# Microphone-Other_Parts.net
KiCad netlist of a schematic drawn in Altium Designer
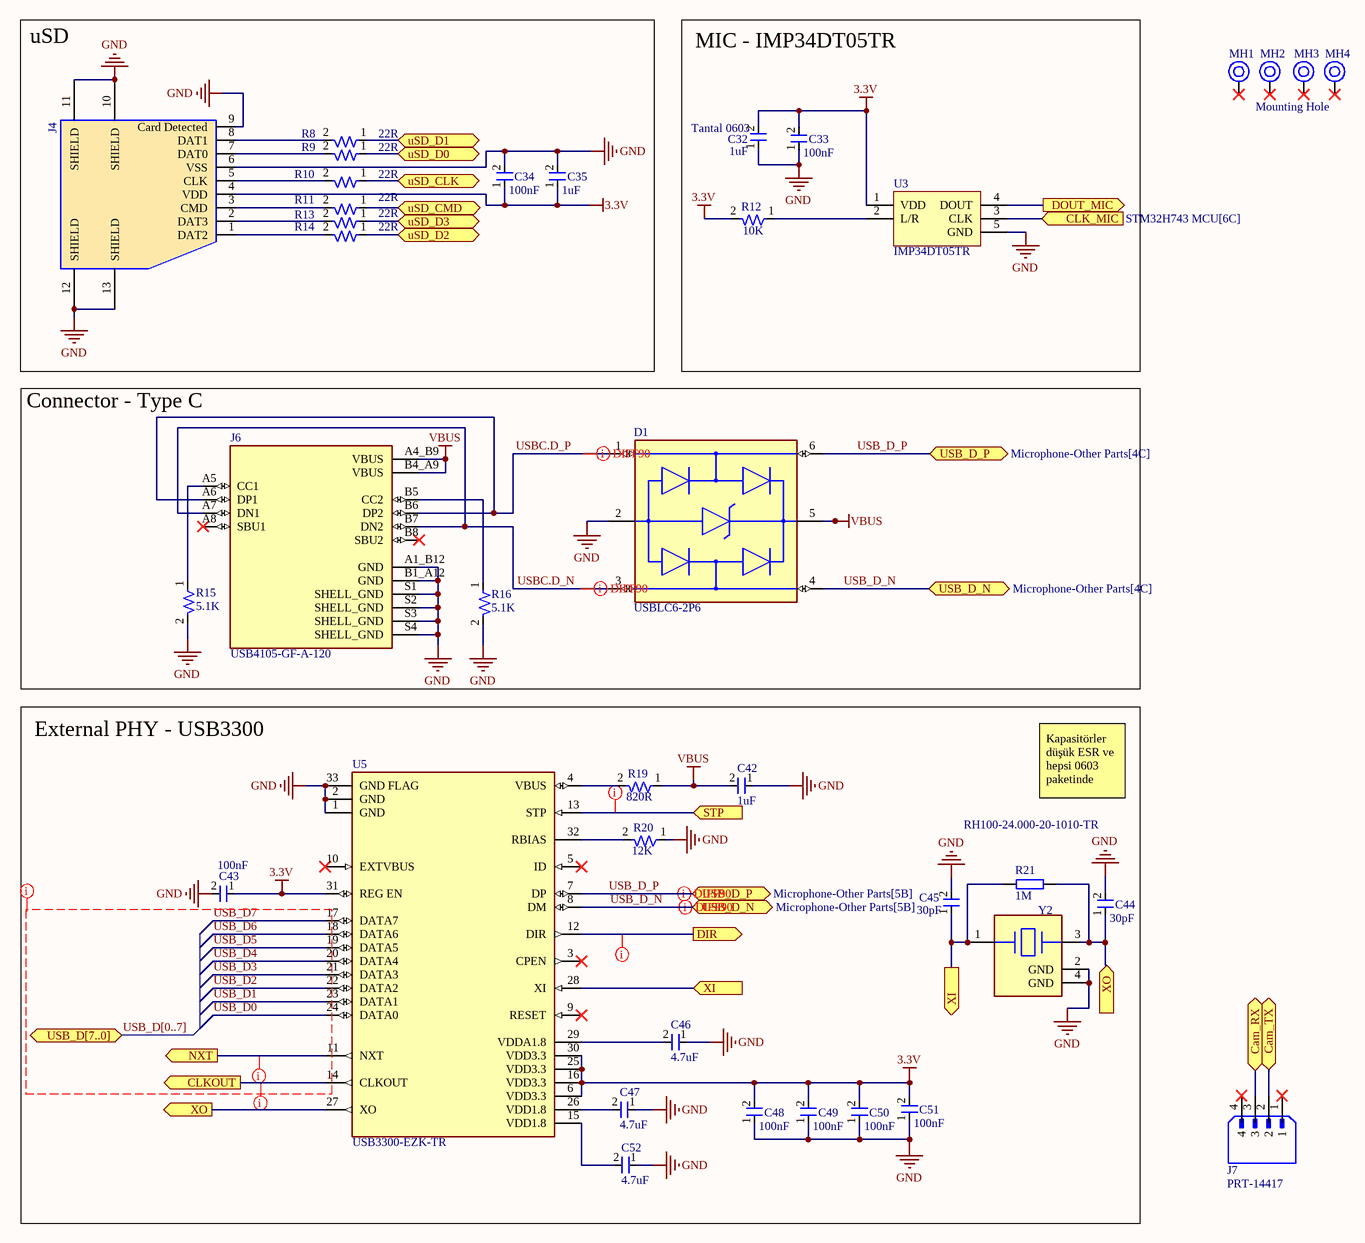
[diagram p0: Microphone-Other Parts.SchDoc]

(export (version "E")
  (design (tool "Eeschema 10.0.6"))
  (components
    (comp (ref "C32")
      (value "Tantal 0603")
      (footprint "0603 Cap")
      (fields (field (name "C") "1uF"))
      (libsource (lib "VoltaRoket") (part "0603 Cap"))
    )
    (comp (ref "C33")
      (value "0603")
      (footprint "0603 Cap")
      (fields (field (name "C") "100nF"))
      (libsource (lib "VoltaRoket") (part "0603 Cap"))
    )
    (comp (ref "C34")
      (value "0603")
      (footprint "0603 Cap")
      (fields (field (name "C") "100nF"))
      (libsource (lib "VoltaRoket") (part "0603 Cap"))
    )
    (comp (ref "C35")
      (value "0603")
      (footprint "0603 Cap")
      (fields (field (name "C") "1uF"))
      (libsource (lib "VoltaRoket") (part "0603 Cap"))
    )
    (comp (ref "C42")
      (value "0603")
      (footprint "0603 Cap")
      (fields (field (name "C") "1uF"))
      (libsource (lib "VoltaRoket") (part "0603 Cap"))
    )
    (comp (ref "C43")
      (value "0603")
      (footprint "0603 Cap")
      (fields (field (name "C") "100nF"))
      (libsource (lib "VoltaRoket") (part "0603 Cap"))
    )
    (comp (ref "C44")
      (value "0603")
      (footprint "0603 Cap")
      (fields (field (name "C") "30pF"))
      (libsource (lib "VoltaRoket") (part "0603 Cap"))
    )
    (comp (ref "C45")
      (value "0603")
      (footprint "0603 Cap")
      (fields (field (name "C") "30pF"))
      (libsource (lib "VoltaRoket") (part "0603 Cap"))
    )
    (comp (ref "C46")
      (value "0603")
      (footprint "0603 Cap")
      (fields (field (name "C") "4.7uF"))
      (libsource (lib "VoltaRoket") (part "0603 Cap"))
    )
    (comp (ref "C47")
      (value "0603")
      (footprint "0603 Cap")
      (fields (field (name "C") "4.7uF"))
      (libsource (lib "VoltaRoket") (part "0603 Cap"))
    )
    (comp (ref "C48")
      (value "0603")
      (footprint "0603 Cap")
      (fields (field (name "C") "100nF"))
      (libsource (lib "VoltaRoket") (part "0603 Cap"))
    )
    (comp (ref "C49")
      (value "0603")
      (footprint "0603 Cap")
      (fields (field (name "C") "100nF"))
      (libsource (lib "VoltaRoket") (part "0603 Cap"))
    )
    (comp (ref "C50")
      (value "0603")
      (footprint "0603 Cap")
      (fields (field (name "C") "100nF"))
      (libsource (lib "VoltaRoket") (part "0603 Cap"))
    )
    (comp (ref "C51")
      (value "0603")
      (footprint "0603 Cap")
      (fields (field (name "C") "100nF"))
      (libsource (lib "VoltaRoket") (part "0603 Cap"))
    )
    (comp (ref "C52")
      (value "0603")
      (footprint "0603 Cap")
      (fields (field (name "C") "4.7uF"))
      (libsource (lib "VoltaRoket") (part "0603 Cap"))
    )
    (comp (ref "D1")
      (value "USBLC6-2P6")
      (footprint "FP-SOT-666-MFG")
      (description "TVS DIODE 5.25V 17V SOT666")
      (libsource (lib "Altium Content Vault") (part "c871e55f7e3243d341edbd671b98d92"))
    )
    (comp (ref "J4")
      (value "KLS1-TF-003-R")
      (footprint "KLS1-TF-003-R")
      (description "KLS1-TF-003-R                     SD CARD CONNECTOR")
      (libsource (lib "VoltaRoket") (part "KLS1-TF-003-R"))
    )
    (comp (ref "J6")
      (value "USB4105-GF-A-120")
      (footprint "GCT_USB4105-GF-A-120")
      (fields (field (name "MF") "Global Connector Technology") (field (name "MP") "USB4105GFA120"))
      (libsource (lib "USB4105-GF-A-120") (part "USB4105-GF-A-120"))
    )
    (comp (ref "J7")
      (value "PRT-14417")
      (footprint "SPARKFUN_PRT-14417")
      (description "QWIIC JST CONNECTOR - SMD 4-PIN")
      (fields (field (name "MF") "SparkFun Electronics"))
      (libsource (lib "PRT-14417 (1)") (part "PRT-14417"))
    )
    (comp (ref "MH1")
      (value "Mounting Hole")
      (footprint "MOUNTING")
      (fields (field (name "MANUFACTURER PART NUMBER") "NA"))
      (libsource (lib "ESTEEMPCBLIB") (part "MH_3.5H_6D"))
    )
    (comp (ref "MH2")
      (value "Mounting Hole")
      (footprint "MOUNTING")
      (fields (field (name "MANUFACTURER PART NUMBER") "NA"))
      (libsource (lib "ESTEEMPCBLIB") (part "MH_3.5H_6D"))
    )
    (comp (ref "MH3")
      (value "Mounting Hole")
      (footprint "MOUNTING")
      (fields (field (name "MANUFACTURER PART NUMBER") "NA"))
      (libsource (lib "ESTEEMPCBLIB") (part "MH_3.5H_6D"))
    )
    (comp (ref "MH4")
      (value "Mounting Hole")
      (footprint "MOUNTING")
      (fields (field (name "MANUFACTURER PART NUMBER") "NA"))
      (libsource (lib "ESTEEMPCBLIB") (part "MH_3.5H_6D"))
    )
    (comp (ref "R8")
      (value "0603")
      (footprint "0603 Res")
      (fields (field (name "R") "22R"))
      (libsource (lib "VoltaRoket") (part "0603 Res"))
    )
    (comp (ref "R9")
      (value "0603")
      (footprint "0603 Res")
      (fields (field (name "R") "22R"))
      (libsource (lib "VoltaRoket") (part "0603 Res"))
    )
    (comp (ref "R10")
      (value "0603")
      (footprint "0603 Res")
      (fields (field (name "R") "22R"))
      (libsource (lib "VoltaRoket") (part "0603 Res"))
    )
    (comp (ref "R11")
      (value "0603")
      (footprint "0603 Res")
      (fields (field (name "R") "22R"))
      (libsource (lib "VoltaRoket") (part "0603 Res"))
    )
    (comp (ref "R12")
      (value "0603")
      (footprint "0603 Res")
      (fields (field (name "R") "10K"))
      (libsource (lib "VoltaRoket") (part "0603 Res"))
    )
    (comp (ref "R13")
      (value "0603")
      (footprint "0603 Res")
      (fields (field (name "R") "22R"))
      (libsource (lib "VoltaRoket") (part "0603 Res"))
    )
    (comp (ref "R14")
      (value "0603")
      (footprint "0603 Res")
      (fields (field (name "R") "22R"))
      (libsource (lib "VoltaRoket") (part "0603 Res"))
    )
    (comp (ref "R15")
      (value "0603")
      (footprint "0603 Res")
      (fields (field (name "R") "5.1K"))
      (libsource (lib "VoltaRoket") (part "0603 Res"))
    )
    (comp (ref "R16")
      (value "0603")
      (footprint "0603 Res")
      (fields (field (name "R") "5.1K"))
      (libsource (lib "VoltaRoket") (part "0603 Res"))
    )
    (comp (ref "R19")
      (value "0603")
      (footprint "0603 Res")
      (fields (field (name "R") "820R"))
      (libsource (lib "VoltaRoket") (part "0603 Res"))
    )
    (comp (ref "R20")
      (value "0603")
      (footprint "0603 Res")
      (fields (field (name "R") "12K"))
      (libsource (lib "VoltaRoket") (part "0603 Res"))
    )
    (comp (ref "R21")
      (value "1M")
      (footprint "RES_0603")
      (description "Resistor SMD 0603")
      (libsource (lib "Phills_Lib") (part "RES_0603"))
    )
    (comp (ref "U3")
      (value "IMP34DT05TR")
      (footprint "HCLGA-4_53_137_15X37_SMD")
      (description "MEMS Microphones AUTO & INDUSTRIAL SENSORS")
      (fields (field (name "MANUFACTURER") "STMicroelectronics"))
      (libsource (lib "ESTEEMPCBLIB") (part "IC_IMP34DT05TR"))
    )
    (comp (ref "U5")
      (value "USB3300-EZK-TR")
      (footprint "FP-32QFN-3304-5X5B-MFG")
      (description "IC CONTROLLER USB 32QFN")
      (fields
        (field (name "MANUFACTURER") "Microchip")
        (field (name "OCTOPART") "https://octopart.com/usb3300-ezk-tr-microchip-24995444")
      )
      (libsource (lib "Altium Content Vault") (part "4aa10816561f241a170599044d3291b"))
    )
    (comp (ref "Y2")
      (value "RH100-24.000-20-1010-TR")
      (footprint "FP-ABM8AIG-MFG")
      (description "Crystal 24MHz ±20ppm (Tol) ±50ppm (Stability) 12pF FUND 50Ω Automotive 4-Pin Ultra Mini-CSMD T/R")
      (libsource (lib "Altium Content Vault") (part "5645ab55de99a04feaa93ac4102b7fe"))
    )
  )
  (nets
    (net (code "1") (name "/CLKOUT") (class "Default")
      (node (ref "U5") (pin "14") (pinfunction "CLKOUT_14") (pintype "output"))
    )
    (net (code "2") (name "/CLK_MIC") (class "Default")
      (node (ref "U3") (pin "3") (pinfunction "CLK_3") (pintype "passive"))
    )
    (net (code "3") (name "/Cam_RX") (class "Default")
      (node (ref "J7") (pin "3") (pinfunction "3_3") (pintype "passive"))
    )
    (net (code "4") (name "/Cam_TX") (class "Default")
      (node (ref "J7") (pin "2") (pinfunction "2_2") (pintype "passive"))
    )
    (net (code "5") (name "/DIR") (class "Default")
      (node (ref "U5") (pin "12") (pinfunction "DIR_12") (pintype "output"))
    )
    (net (code "6") (name "/DOUT_MIC") (class "Default")
      (node (ref "U3") (pin "4") (pinfunction "DOUT_4") (pintype "passive"))
    )
    (net (code "7") (name "/NXT") (class "Default")
      (node (ref "U5") (pin "11") (pinfunction "NXT_11") (pintype "output"))
    )
    (net (code "8") (name "/STP") (class "Default")
      (node (ref "U5") (pin "13") (pinfunction "STP_13") (pintype "input"))
    )
    (net (code "9") (name "/USBC.D_N") (class "Default")
      (node (ref "D1") (pin "3") (pinfunction "I/O2_3") (pintype "bidirectional"))
      (node (ref "J6") (pin "A7") (pinfunction "DN1_A7") (pintype "bidirectional"))
      (node (ref "J6") (pin "B7") (pinfunction "DN2_B7") (pintype "bidirectional"))
    )
    (net (code "10") (name "/USBC.D_P") (class "Default")
      (node (ref "D1") (pin "1") (pinfunction "I/O1_1") (pintype "bidirectional"))
      (node (ref "J6") (pin "A6") (pinfunction "DP1_A6") (pintype "bidirectional"))
      (node (ref "J6") (pin "B6") (pinfunction "DP2_B6") (pintype "bidirectional"))
    )
    (net (code "11") (name "/USB_D0") (class "Default")
      (node (ref "U5") (pin "24") (pinfunction "DATA0_24") (pintype "bidirectional"))
    )
    (net (code "12") (name "/USB_D1") (class "Default")
      (node (ref "U5") (pin "23") (pinfunction "DATA1_23") (pintype "bidirectional"))
    )
    (net (code "13") (name "/USB_D2") (class "Default")
      (node (ref "U5") (pin "22") (pinfunction "DATA2_22") (pintype "bidirectional"))
    )
    (net (code "14") (name "/USB_D3") (class "Default")
      (node (ref "U5") (pin "21") (pinfunction "DATA3_21") (pintype "bidirectional"))
    )
    (net (code "15") (name "/USB_D4") (class "Default")
      (node (ref "U5") (pin "20") (pinfunction "DATA4_20") (pintype "bidirectional"))
    )
    (net (code "16") (name "/USB_D5") (class "Default")
      (node (ref "U5") (pin "19") (pinfunction "DATA5_19") (pintype "bidirectional"))
    )
    (net (code "17") (name "/USB_D6") (class "Default")
      (node (ref "U5") (pin "18") (pinfunction "DATA6_18") (pintype "bidirectional"))
    )
    (net (code "18") (name "/USB_D7") (class "Default")
      (node (ref "U5") (pin "17") (pinfunction "DATA7_17") (pintype "bidirectional"))
    )
    (net (code "20") (name "/USB_D_N") (class "Default")
      (node (ref "D1") (pin "4") (pinfunction "I/O2_4") (pintype "bidirectional"))
      (node (ref "U5") (pin "8") (pinfunction "DM_8") (pintype "bidirectional"))
    )
    (net (code "21") (name "/USB_D_P") (class "Default")
      (node (ref "D1") (pin "6") (pinfunction "I/O1_6") (pintype "bidirectional"))
      (node (ref "U5") (pin "7") (pinfunction "DP_7") (pintype "bidirectional"))
    )
    (net (code "22") (name "/XI") (class "Default")
      (node (ref "C45") (pin "1") (pinfunction "1_1") (pintype "passive"))
      (node (ref "R21") (pin "1") (pinfunction "1_1") (pintype "passive"))
      (node (ref "U5") (pin "28") (pinfunction "XI_28") (pintype "input"))
      (node (ref "Y2") (pin "1") (pinfunction "1_1") (pintype "passive"))
    )
    (net (code "23") (name "/XO") (class "Default")
      (node (ref "C44") (pin "1") (pinfunction "1_1") (pintype "passive"))
      (node (ref "R21") (pin "2") (pinfunction "2_2") (pintype "passive"))
      (node (ref "U5") (pin "27") (pinfunction "XO_27") (pintype "output"))
      (node (ref "Y2") (pin "3") (pinfunction "3_3") (pintype "passive"))
    )
    (net (code "24") (name "/uSD_CLK") (class "Default")
      (node (ref "R10") (pin "1") (pinfunction "1_1") (pintype "passive"))
    )
    (net (code "25") (name "/uSD_CMD") (class "Default")
      (node (ref "R11") (pin "1") (pinfunction "1_1") (pintype "passive"))
    )
    (net (code "26") (name "/uSD_D0") (class "Default")
      (node (ref "R9") (pin "1") (pinfunction "1_1") (pintype "passive"))
    )
    (net (code "27") (name "/uSD_D1") (class "Default")
      (node (ref "R8") (pin "1") (pinfunction "1_1") (pintype "passive"))
    )
    (net (code "28") (name "/uSD_D2") (class "Default")
      (node (ref "R14") (pin "1") (pinfunction "1_1") (pintype "passive"))
    )
    (net (code "29") (name "/uSD_D3") (class "Default")
      (node (ref "R13") (pin "1") (pinfunction "1_1") (pintype "passive"))
    )
    (net (code "30") (name "3.3V") (class "Default")
      (node (ref "C32") (pin "2") (pinfunction "2_2") (pintype "passive"))
      (node (ref "C33") (pin "2") (pinfunction "2_2") (pintype "passive"))
      (node (ref "C34") (pin "1") (pinfunction "1_1") (pintype "passive"))
      (node (ref "C35") (pin "1") (pinfunction "1_1") (pintype "passive"))
      (node (ref "C43") (pin "1") (pinfunction "1_1") (pintype "passive"))
      (node (ref "C48") (pin "2") (pinfunction "2_2") (pintype "passive"))
      (node (ref "C49") (pin "2") (pinfunction "2_2") (pintype "passive"))
      (node (ref "C50") (pin "2") (pinfunction "2_2") (pintype "passive"))
      (node (ref "C51") (pin "2") (pinfunction "2_2") (pintype "passive"))
      (node (ref "J4") (pin "4") (pinfunction "VDD_4") (pintype "passive"))
      (node (ref "R12") (pin "2") (pinfunction "2_2") (pintype "passive"))
      (node (ref "U3") (pin "1") (pinfunction "VDD_1") (pintype "passive"))
      (node (ref "U5") (pin "16") (pinfunction "VDD3.3_16") (pintype "power_in"))
      (node (ref "U5") (pin "25") (pinfunction "VDD3.3_25") (pintype "power_in"))
      (node (ref "U5") (pin "30") (pinfunction "VDD3.3_30") (pintype "power_in"))
      (node (ref "U5") (pin "31") (pinfunction "REG_EN_31") (pintype "bidirectional"))
      (node (ref "U5") (pin "6") (pinfunction "VDD3.3_6") (pintype "power_in"))
    )
    (net (code "31") (name "GND") (class "Default")
      (node (ref "C32") (pin "1") (pinfunction "1_1") (pintype "passive"))
      (node (ref "C33") (pin "1") (pinfunction "1_1") (pintype "passive"))
      (node (ref "C34") (pin "2") (pinfunction "2_2") (pintype "passive"))
      (node (ref "C35") (pin "2") (pinfunction "2_2") (pintype "passive"))
      (node (ref "C42") (pin "1") (pinfunction "1_1") (pintype "passive"))
      (node (ref "C43") (pin "2") (pinfunction "2_2") (pintype "passive"))
      (node (ref "C44") (pin "2") (pinfunction "2_2") (pintype "passive"))
      (node (ref "C45") (pin "2") (pinfunction "2_2") (pintype "passive"))
      (node (ref "C46") (pin "1") (pinfunction "1_1") (pintype "passive"))
      (node (ref "C47") (pin "1") (pinfunction "1_1") (pintype "passive"))
      (node (ref "C48") (pin "1") (pinfunction "1_1") (pintype "passive"))
      (node (ref "C49") (pin "1") (pinfunction "1_1") (pintype "passive"))
      (node (ref "C50") (pin "1") (pinfunction "1_1") (pintype "passive"))
      (node (ref "C51") (pin "1") (pinfunction "1_1") (pintype "passive"))
      (node (ref "C52") (pin "1") (pinfunction "1_1") (pintype "passive"))
      (node (ref "D1") (pin "2") (pinfunction "GND_2") (pintype "power_in"))
      (node (ref "J4") (pin "10") (pinfunction "SHIELD_10") (pintype "passive"))
      (node (ref "J4") (pin "11") (pinfunction "SHIELD_11") (pintype "passive"))
      (node (ref "J4") (pin "12") (pinfunction "SHIELD_12") (pintype "passive"))
      (node (ref "J4") (pin "13") (pinfunction "SHIELD_13") (pintype "passive"))
      (node (ref "J4") (pin "6") (pinfunction "VSS_6") (pintype "passive"))
      (node (ref "J4") (pin "9") (pinfunction "Card_Detected_9") (pintype "passive"))
      (node (ref "J6") (pin "A1_B12") (pinfunction "GND_A1_B12") (pintype "power_in"))
      (node (ref "J6") (pin "B1_A12") (pinfunction "GND_B1_A12") (pintype "power_in"))
      (node (ref "J6") (pin "S1") (pinfunction "SHELL_GND_S1") (pintype "power_in"))
      (node (ref "J6") (pin "S2") (pinfunction "SHELL_GND_S2") (pintype "power_in"))
      (node (ref "J6") (pin "S3") (pinfunction "SHELL_GND_S3") (pintype "power_in"))
      (node (ref "J6") (pin "S4") (pinfunction "SHELL_GND_S4") (pintype "power_in"))
      (node (ref "R15") (pin "2") (pinfunction "2_2") (pintype "passive"))
      (node (ref "R16") (pin "2") (pinfunction "2_2") (pintype "passive"))
      (node (ref "R20") (pin "1") (pinfunction "1_1") (pintype "passive"))
      (node (ref "U3") (pin "5") (pinfunction "GND_5") (pintype "passive"))
      (node (ref "U5") (pin "1") (pinfunction "GND_1") (pintype "power_in"))
      (node (ref "U5") (pin "2") (pinfunction "GND_2") (pintype "power_in"))
      (node (ref "U5") (pin "33") (pinfunction "GND_FLAG_33") (pintype "power_in"))
      (node (ref "Y2") (pin "2") (pinfunction "GND_2") (pintype "power_in"))
      (node (ref "Y2") (pin "4") (pinfunction "GND_4") (pintype "power_in"))
    )
    (net (code "32") (name "Net-(C47-Pad2)") (class "Default")
      (node (ref "C47") (pin "2") (pinfunction "2_2") (pintype "passive"))
      (node (ref "U5") (pin "26") (pinfunction "VDD1.8_26") (pintype "power_in"))
    )
    (net (code "33") (name "Net-(C52-Pad2)") (class "Default")
      (node (ref "C52") (pin "2") (pinfunction "2_2") (pintype "passive"))
      (node (ref "U5") (pin "15") (pinfunction "VDD1.8_15") (pintype "power_in"))
    )
    (net (code "34") (name "Net-(J4-CLK)") (class "Default")
      (node (ref "J4") (pin "5") (pinfunction "CLK_5") (pintype "passive"))
      (node (ref "R10") (pin "2") (pinfunction "2_2") (pintype "passive"))
    )
    (net (code "35") (name "Net-(J4-CMD)") (class "Default")
      (node (ref "J4") (pin "3") (pinfunction "CMD_3") (pintype "passive"))
      (node (ref "R11") (pin "2") (pinfunction "2_2") (pintype "passive"))
    )
    (net (code "36") (name "Net-(J4-DAT0)") (class "Default")
      (node (ref "J4") (pin "7") (pinfunction "DAT0_7") (pintype "passive"))
      (node (ref "R9") (pin "2") (pinfunction "2_2") (pintype "passive"))
    )
    (net (code "37") (name "Net-(J4-DAT1)") (class "Default")
      (node (ref "J4") (pin "8") (pinfunction "DAT1_8") (pintype "passive"))
      (node (ref "R8") (pin "2") (pinfunction "2_2") (pintype "passive"))
    )
    (net (code "38") (name "Net-(J4-DAT2)") (class "Default")
      (node (ref "J4") (pin "1") (pinfunction "DAT2_1") (pintype "passive"))
      (node (ref "R14") (pin "2") (pinfunction "2_2") (pintype "passive"))
    )
    (net (code "39") (name "Net-(J4-DAT3)") (class "Default")
      (node (ref "J4") (pin "2") (pinfunction "DAT3_2") (pintype "passive"))
      (node (ref "R13") (pin "2") (pinfunction "2_2") (pintype "passive"))
    )
    (net (code "40") (name "Net-(J6-CC1)") (class "Default")
      (node (ref "J6") (pin "A5") (pinfunction "CC1_A5") (pintype "bidirectional"))
      (node (ref "R15") (pin "1") (pinfunction "1_1") (pintype "passive"))
    )
    (net (code "41") (name "Net-(J6-CC2)") (class "Default")
      (node (ref "J6") (pin "B5") (pinfunction "CC2_B5") (pintype "bidirectional"))
      (node (ref "R16") (pin "1") (pinfunction "1_1") (pintype "passive"))
    )
    (net (code "42") (name "Net-(U3-L{slash}R)") (class "Default")
      (node (ref "R12") (pin "1") (pinfunction "1_1") (pintype "passive"))
      (node (ref "U3") (pin "2") (pinfunction "L/R_2") (pintype "passive"))
    )
    (net (code "43") (name "Net-(U5-RBIAS)") (class "Default")
      (node (ref "R20") (pin "2") (pinfunction "2_2") (pintype "passive"))
      (node (ref "U5") (pin "32") (pinfunction "RBIAS_32") (pintype "power_in"))
    )
    (net (code "44") (name "Net-(U5-VBUS)") (class "Default")
      (node (ref "R19") (pin "2") (pinfunction "2_2") (pintype "passive"))
      (node (ref "U5") (pin "4") (pinfunction "VBUS_4") (pintype "bidirectional"))
    )
    (net (code "45") (name "Net-(U5-VDDA1.8)") (class "Default")
      (node (ref "C46") (pin "2") (pinfunction "2_2") (pintype "passive"))
      (node (ref "U5") (pin "29") (pinfunction "VDDA1.8_29") (pintype "power_in"))
    )
    (net (code "46") (name "VBUS") (class "Default")
      (node (ref "C42") (pin "2") (pinfunction "2_2") (pintype "passive"))
      (node (ref "D1") (pin "5") (pinfunction "VBUS_5") (pintype "power_in"))
      (node (ref "J6") (pin "A4_B9") (pinfunction "VBUS_A4_B9") (pintype "power_in"))
      (node (ref "J6") (pin "B4_A9") (pinfunction "VBUS_B4_A9") (pintype "power_in"))
      (node (ref "R19") (pin "1") (pinfunction "1_1") (pintype "passive"))
    )
    (net (code "47") (name "unconnected-(J6-SBU1-PadA8)") (class "Default")
      (node (ref "J6") (pin "A8") (pinfunction "SBU1_A8") (pintype "bidirectional+no_connect"))
    )
    (net (code "48") (name "unconnected-(J6-SBU2-PadB8)") (class "Default")
      (node (ref "J6") (pin "B8") (pinfunction "SBU2_B8") (pintype "bidirectional+no_connect"))
    )
    (net (code "49") (name "unconnected-(J7-Pad1)") (class "Default")
      (node (ref "J7") (pin "1") (pinfunction "1_1") (pintype "passive+no_connect"))
    )
    (net (code "50") (name "unconnected-(J7-Pad4)") (class "Default")
      (node (ref "J7") (pin "4") (pinfunction "4_4") (pintype "passive+no_connect"))
    )
    (net (code "51") (name "unconnected-(MH1-Pad1)") (class "Default")
      (node (ref "MH1") (pin "1") (pinfunction "1_1") (pintype "passive+no_connect"))
    )
    (net (code "52") (name "unconnected-(MH2-Pad1)") (class "Default")
      (node (ref "MH2") (pin "1") (pinfunction "1_1") (pintype "passive+no_connect"))
    )
    (net (code "53") (name "unconnected-(MH3-Pad1)") (class "Default")
      (node (ref "MH3") (pin "1") (pinfunction "1_1") (pintype "passive+no_connect"))
    )
    (net (code "54") (name "unconnected-(MH4-Pad1)") (class "Default")
      (node (ref "MH4") (pin "1") (pinfunction "1_1") (pintype "passive+no_connect"))
    )
    (net (code "55") (name "unconnected-(U5-CPEN-Pad3)") (class "Default")
      (node (ref "U5") (pin "3") (pinfunction "CPEN_3") (pintype "output+no_connect"))
    )
    (net (code "56") (name "unconnected-(U5-EXTVBUS-Pad10)") (class "Default")
      (node (ref "U5") (pin "10") (pinfunction "EXTVBUS_10") (pintype "input+no_connect"))
    )
    (net (code "57") (name "unconnected-(U5-ID-Pad5)") (class "Default")
      (node (ref "U5") (pin "5") (pinfunction "ID_5") (pintype "input+no_connect"))
    )
    (net (code "58") (name "unconnected-(U5-RESET-Pad9)") (class "Default")
      (node (ref "U5") (pin "9") (pinfunction "RESET_9") (pintype "input+no_connect"))
    )
  )
)
